# psu_and_discharge.net
KiCad netlist of a schematic drawn in Altium Designer
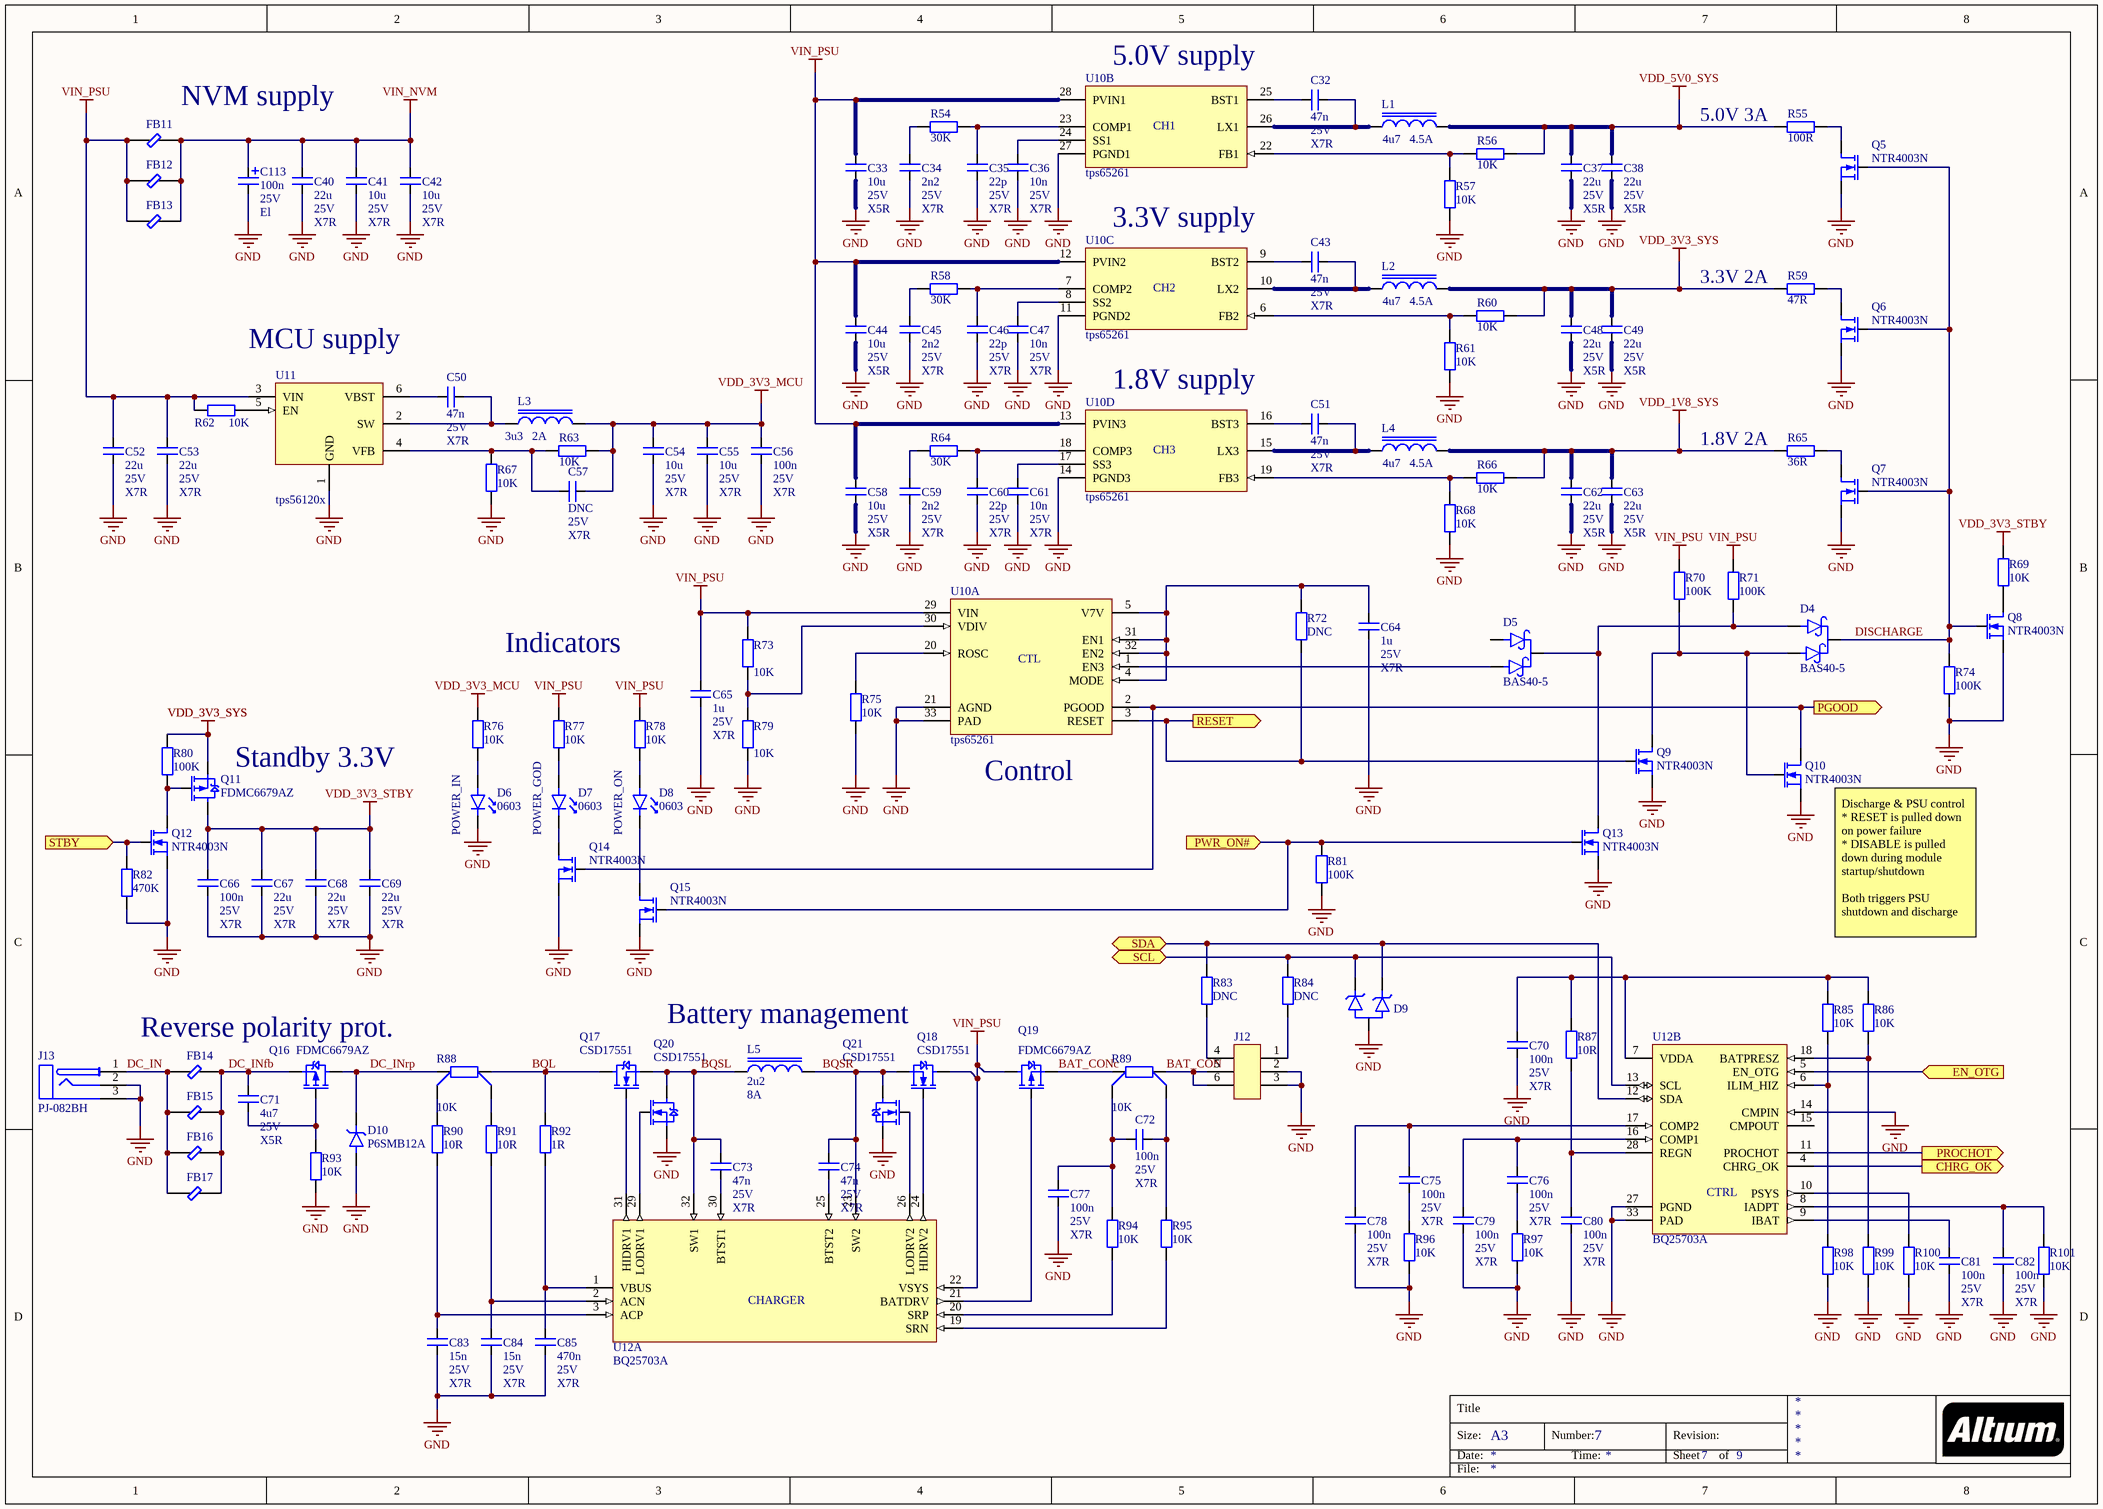
[diagram p0: psu_and_discharge.SchDoc]

(export (version "E")
  (design (tool "Eeschema 10.0.6"))
  (components
    (comp (ref "C32")
      (value "47n")
      (footprint "C1005[0402]")
      (description "Capacitor")
      (fields (field (name "VOLTAGE") "25V") (field (name "TYPE") "X7R") (field (name "Comment") "cap"))
      (libsource (lib "gpa_passives") (part "cap"))
    )
    (comp (ref "C33")
      (value "10u")
      (footprint "C3216[1206]")
      (description "Capacitor")
      (fields (field (name "VOLTAGE") "25V") (field (name "TYPE") "X5R") (field (name "Comment") "cap"))
      (libsource (lib "gpa_passives") (part "cap"))
    )
    (comp (ref "C34")
      (value "2n2")
      (footprint "C1005[0402]")
      (description "Capacitor")
      (fields (field (name "VOLTAGE") "25V") (field (name "TYPE") "X7R") (field (name "Comment") "cap"))
      (libsource (lib "gpa_passives") (part "cap"))
    )
    (comp (ref "C35")
      (value "22p")
      (footprint "C1005[0402]")
      (description "Capacitor")
      (fields (field (name "VOLTAGE") "25V") (field (name "TYPE") "X7R") (field (name "Comment") "cap"))
      (libsource (lib "gpa_passives") (part "cap"))
    )
    (comp (ref "C36")
      (value "10n")
      (footprint "C1005[0402]")
      (description "Capacitor")
      (fields (field (name "VOLTAGE") "25V") (field (name "TYPE") "X7R") (field (name "Comment") "cap"))
      (libsource (lib "gpa_passives") (part "cap"))
    )
    (comp (ref "C37")
      (value "22u")
      (footprint "C3216[1206]")
      (description "Capacitor")
      (fields (field (name "VOLTAGE") "25V") (field (name "TYPE") "X5R") (field (name "Comment") "cap"))
      (libsource (lib "gpa_passives") (part "cap"))
    )
    (comp (ref "C38")
      (value "22u")
      (footprint "C3216[1206]")
      (description "Capacitor")
      (fields (field (name "VOLTAGE") "25V") (field (name "TYPE") "X5R") (field (name "Comment") "cap"))
      (libsource (lib "gpa_passives") (part "cap"))
    )
    (comp (ref "C40")
      (value "22u")
      (footprint "C3216[1206]")
      (description "Capacitor")
      (fields (field (name "VOLTAGE") "25V") (field (name "TYPE") "X7R") (field (name "Comment") "cap"))
      (libsource (lib "gpa_passives") (part "cap"))
    )
    (comp (ref "C41")
      (value "10u")
      (footprint "C3216[1206]")
      (description "Capacitor")
      (fields (field (name "VOLTAGE") "25V") (field (name "TYPE") "X7R") (field (name "Comment") "cap"))
      (libsource (lib "gpa_passives") (part "cap"))
    )
    (comp (ref "C42")
      (value "10u")
      (footprint "C3216[1206]")
      (description "Capacitor")
      (fields (field (name "VOLTAGE") "25V") (field (name "TYPE") "X7R") (field (name "Comment") "cap"))
      (libsource (lib "gpa_passives") (part "cap"))
    )
    (comp (ref "C43")
      (value "47n")
      (footprint "C1005[0402]")
      (description "Capacitor")
      (fields (field (name "VOLTAGE") "25V") (field (name "TYPE") "X7R") (field (name "Comment") "cap"))
      (libsource (lib "gpa_passives") (part "cap"))
    )
    (comp (ref "C44")
      (value "10u")
      (footprint "C3216[1206]")
      (description "Capacitor")
      (fields (field (name "VOLTAGE") "25V") (field (name "TYPE") "X5R") (field (name "Comment") "cap"))
      (libsource (lib "gpa_passives") (part "cap"))
    )
    (comp (ref "C45")
      (value "2n2")
      (footprint "C1005[0402]")
      (description "Capacitor")
      (fields (field (name "VOLTAGE") "25V") (field (name "TYPE") "X7R") (field (name "Comment") "cap"))
      (libsource (lib "gpa_passives") (part "cap"))
    )
    (comp (ref "C46")
      (value "22p")
      (footprint "C1005[0402]")
      (description "Capacitor")
      (fields (field (name "VOLTAGE") "25V") (field (name "TYPE") "X7R") (field (name "Comment") "cap"))
      (libsource (lib "gpa_passives") (part "cap"))
    )
    (comp (ref "C47")
      (value "10n")
      (footprint "C1005[0402]")
      (description "Capacitor")
      (fields (field (name "VOLTAGE") "25V") (field (name "TYPE") "X7R") (field (name "Comment") "cap"))
      (libsource (lib "gpa_passives") (part "cap"))
    )
    (comp (ref "C48")
      (value "22u")
      (footprint "C3216[1206]")
      (description "Capacitor")
      (fields (field (name "VOLTAGE") "25V") (field (name "TYPE") "X5R") (field (name "Comment") "cap"))
      (libsource (lib "gpa_passives") (part "cap"))
    )
    (comp (ref "C49")
      (value "22u")
      (footprint "C3216[1206]")
      (description "Capacitor")
      (fields (field (name "VOLTAGE") "25V") (field (name "TYPE") "X5R") (field (name "Comment") "cap"))
      (libsource (lib "gpa_passives") (part "cap"))
    )
    (comp (ref "C50")
      (value "47n")
      (footprint "C1005[0402]")
      (description "Capacitor")
      (fields (field (name "VOLTAGE") "25V") (field (name "TYPE") "X7R") (field (name "Comment") "cap"))
      (libsource (lib "gpa_passives") (part "cap"))
    )
    (comp (ref "C51")
      (value "47n")
      (footprint "C1005[0402]")
      (description "Capacitor")
      (fields (field (name "VOLTAGE") "25V") (field (name "TYPE") "X7R") (field (name "Comment") "cap"))
      (libsource (lib "gpa_passives") (part "cap"))
    )
    (comp (ref "C52")
      (value "22u")
      (footprint "C3216[1206]")
      (description "Capacitor")
      (fields (field (name "VOLTAGE") "25V") (field (name "TYPE") "X7R") (field (name "Comment") "cap"))
      (libsource (lib "gpa_passives") (part "cap"))
    )
    (comp (ref "C53")
      (value "22u")
      (footprint "C3216[1206]")
      (description "Capacitor")
      (fields (field (name "VOLTAGE") "25V") (field (name "TYPE") "X7R") (field (name "Comment") "cap"))
      (libsource (lib "gpa_passives") (part "cap"))
    )
    (comp (ref "C54")
      (value "10u")
      (footprint "C3216[1206]")
      (description "Capacitor")
      (fields (field (name "VOLTAGE") "25V") (field (name "TYPE") "X7R") (field (name "Comment") "cap"))
      (libsource (lib "gpa_passives") (part "cap"))
    )
    (comp (ref "C55")
      (value "10u")
      (footprint "C3216[1206]")
      (description "Capacitor")
      (fields (field (name "VOLTAGE") "25V") (field (name "TYPE") "X7R") (field (name "Comment") "cap"))
      (libsource (lib "gpa_passives") (part "cap"))
    )
    (comp (ref "C56")
      (value "100n")
      (footprint "C1005[0402]")
      (description "Capacitor")
      (fields (field (name "VOLTAGE") "25V") (field (name "TYPE") "X7R") (field (name "Comment") "cap"))
      (libsource (lib "gpa_passives") (part "cap"))
    )
    (comp (ref "C57")
      (value "DNC")
      (footprint "C1005[0402]")
      (description "Capacitor")
      (fields (field (name "VOLTAGE") "25V") (field (name "TYPE") "X7R") (field (name "Comment") "cap"))
      (libsource (lib "gpa_passives") (part "cap"))
    )
    (comp (ref "C58")
      (value "10u")
      (footprint "C3216[1206]")
      (description "Capacitor")
      (fields (field (name "VOLTAGE") "25V") (field (name "TYPE") "X5R") (field (name "Comment") "cap"))
      (libsource (lib "gpa_passives") (part "cap"))
    )
    (comp (ref "C59")
      (value "2n2")
      (footprint "C1005[0402]")
      (description "Capacitor")
      (fields (field (name "VOLTAGE") "25V") (field (name "TYPE") "X7R") (field (name "Comment") "cap"))
      (libsource (lib "gpa_passives") (part "cap"))
    )
    (comp (ref "C60")
      (value "22p")
      (footprint "C1005[0402]")
      (description "Capacitor")
      (fields (field (name "VOLTAGE") "25V") (field (name "TYPE") "X7R") (field (name "Comment") "cap"))
      (libsource (lib "gpa_passives") (part "cap"))
    )
    (comp (ref "C61")
      (value "10n")
      (footprint "C1005[0402]")
      (description "Capacitor")
      (fields (field (name "VOLTAGE") "25V") (field (name "TYPE") "X7R") (field (name "Comment") "cap"))
      (libsource (lib "gpa_passives") (part "cap"))
    )
    (comp (ref "C62")
      (value "22u")
      (footprint "C3216[1206]")
      (description "Capacitor")
      (fields (field (name "VOLTAGE") "25V") (field (name "TYPE") "X5R") (field (name "Comment") "cap"))
      (libsource (lib "gpa_passives") (part "cap"))
    )
    (comp (ref "C63")
      (value "22u")
      (footprint "C3216[1206]")
      (description "Capacitor")
      (fields (field (name "VOLTAGE") "25V") (field (name "TYPE") "X5R") (field (name "Comment") "cap"))
      (libsource (lib "gpa_passives") (part "cap"))
    )
    (comp (ref "C64")
      (value "1u")
      (footprint "C2012[0805]")
      (description "Capacitor")
      (fields (field (name "VOLTAGE") "25V") (field (name "TYPE") "X7R") (field (name "Comment") "cap"))
      (libsource (lib "gpa_passives") (part "cap"))
    )
    (comp (ref "C65")
      (value "1u")
      (footprint "C2012[0805]")
      (description "Capacitor")
      (fields (field (name "VOLTAGE") "25V") (field (name "TYPE") "X7R") (field (name "Comment") "cap"))
      (libsource (lib "gpa_passives") (part "cap"))
    )
    (comp (ref "C66")
      (value "100n")
      (footprint "C1005[0402]")
      (description "Capacitor")
      (fields (field (name "VOLTAGE") "25V") (field (name "TYPE") "X7R") (field (name "Comment") "cap"))
      (libsource (lib "gpa_passives") (part "cap"))
    )
    (comp (ref "C67")
      (value "22u")
      (footprint "C1005[0402]")
      (description "Capacitor")
      (fields (field (name "VOLTAGE") "25V") (field (name "TYPE") "X7R") (field (name "Comment") "cap"))
      (libsource (lib "gpa_passives") (part "cap"))
    )
    (comp (ref "C68")
      (value "22u")
      (footprint "C1005[0402]")
      (description "Capacitor")
      (fields (field (name "VOLTAGE") "25V") (field (name "TYPE") "X7R") (field (name "Comment") "cap"))
      (libsource (lib "gpa_passives") (part "cap"))
    )
    (comp (ref "C69")
      (value "22u")
      (footprint "C1005[0402]")
      (description "Capacitor")
      (fields (field (name "VOLTAGE") "25V") (field (name "TYPE") "X7R") (field (name "Comment") "cap"))
      (libsource (lib "gpa_passives") (part "cap"))
    )
    (comp (ref "C70")
      (value "100n")
      (footprint "C1005[0402]")
      (description "Capacitor")
      (fields (field (name "VOLTAGE") "25V") (field (name "TYPE") "X7R") (field (name "Comment") "cap"))
      (libsource (lib "gpa_passives") (part "cap"))
    )
    (comp (ref "C71")
      (value "4u7")
      (footprint "C1005[0402]")
      (description "Capacitor")
      (fields (field (name "VOLTAGE") "25V") (field (name "TYPE") "X5R") (field (name "Comment") "cap"))
      (libsource (lib "gpa_passives") (part "cap"))
    )
    (comp (ref "C72")
      (value "100n")
      (footprint "C1005[0402]")
      (description "Capacitor")
      (fields (field (name "VOLTAGE") "25V") (field (name "TYPE") "X7R") (field (name "Comment") "cap"))
      (libsource (lib "gpa_passives") (part "cap"))
    )
    (comp (ref "C73")
      (value "47n")
      (footprint "C1005[0402]")
      (description "Capacitor")
      (fields (field (name "VOLTAGE") "25V") (field (name "TYPE") "X7R") (field (name "Comment") "cap"))
      (libsource (lib "gpa_passives") (part "cap"))
    )
    (comp (ref "C74")
      (value "47n")
      (footprint "C1005[0402]")
      (description "Capacitor")
      (fields (field (name "VOLTAGE") "25V") (field (name "TYPE") "X7R") (field (name "Comment") "cap"))
      (libsource (lib "gpa_passives") (part "cap"))
    )
    (comp (ref "C75")
      (value "100n")
      (footprint "C1005[0402]")
      (description "Capacitor")
      (fields (field (name "VOLTAGE") "25V") (field (name "TYPE") "X7R") (field (name "Comment") "cap"))
      (libsource (lib "gpa_passives") (part "cap"))
    )
    (comp (ref "C76")
      (value "100n")
      (footprint "C1005[0402]")
      (description "Capacitor")
      (fields (field (name "VOLTAGE") "25V") (field (name "TYPE") "X7R") (field (name "Comment") "cap"))
      (libsource (lib "gpa_passives") (part "cap"))
    )
    (comp (ref "C77")
      (value "100n")
      (footprint "C1005[0402]")
      (description "Capacitor")
      (fields (field (name "VOLTAGE") "25V") (field (name "TYPE") "X7R") (field (name "Comment") "cap"))
      (libsource (lib "gpa_passives") (part "cap"))
    )
    (comp (ref "C78")
      (value "100n")
      (footprint "C1005[0402]")
      (description "Capacitor")
      (fields (field (name "VOLTAGE") "25V") (field (name "TYPE") "X7R") (field (name "Comment") "cap"))
      (libsource (lib "gpa_passives") (part "cap"))
    )
    (comp (ref "C79")
      (value "100n")
      (footprint "C1005[0402]")
      (description "Capacitor")
      (fields (field (name "VOLTAGE") "25V") (field (name "TYPE") "X7R") (field (name "Comment") "cap"))
      (libsource (lib "gpa_passives") (part "cap"))
    )
    (comp (ref "C80")
      (value "100n")
      (footprint "C1005[0402]")
      (description "Capacitor")
      (fields (field (name "VOLTAGE") "25V") (field (name "TYPE") "X7R") (field (name "Comment") "cap"))
      (libsource (lib "gpa_passives") (part "cap"))
    )
    (comp (ref "C81")
      (value "100n")
      (footprint "C1005[0402]")
      (description "Capacitor")
      (fields (field (name "VOLTAGE") "25V") (field (name "TYPE") "X7R") (field (name "Comment") "cap"))
      (libsource (lib "gpa_passives") (part "cap"))
    )
    (comp (ref "C82")
      (value "100n")
      (footprint "C1005[0402]")
      (description "Capacitor")
      (fields (field (name "VOLTAGE") "25V") (field (name "TYPE") "X7R") (field (name "Comment") "cap"))
      (libsource (lib "gpa_passives") (part "cap"))
    )
    (comp (ref "C83")
      (value "15n")
      (footprint "C1005[0402]")
      (description "Capacitor")
      (fields (field (name "VOLTAGE") "25V") (field (name "TYPE") "X7R") (field (name "Comment") "cap"))
      (libsource (lib "gpa_passives") (part "cap"))
    )
    (comp (ref "C84")
      (value "15n")
      (footprint "C1005[0402]")
      (description "Capacitor")
      (fields (field (name "VOLTAGE") "25V") (field (name "TYPE") "X7R") (field (name "Comment") "cap"))
      (libsource (lib "gpa_passives") (part "cap"))
    )
    (comp (ref "C85")
      (value "470n")
      (footprint "C1005[0402]")
      (description "Capacitor")
      (fields (field (name "VOLTAGE") "25V") (field (name "TYPE") "X7R") (field (name "Comment") "cap"))
      (libsource (lib "gpa_passives") (part "cap"))
    )
    (comp (ref "C113")
      (value "100n")
      (footprint "CAPAE7366X55M")
      (description "Polarized capacitor")
      (fields (field (name "VOLTAGE") "25V") (field (name "TYPE") "El") (field (name "Comment") "pcap"))
      (libsource (lib "gpa_passives") (part "pcap"))
    )
    (comp (ref "D4")
      (value "BAS40-5")
      (footprint "DCC_SOT95P235X110-3N")
      (libsource (lib "gpa_actives") (part "diode_dual_cc"))
    )
    (comp (ref "D5")
      (value "BAS40-5")
      (footprint "DCC_SOT95P235X110-3N")
      (libsource (lib "gpa_actives") (part "diode_dual_cc"))
    )
    (comp (ref "D6")
      (value "0603")
      (footprint "LEDC1608X06N")
      (libsource (lib "gpa_actives") (part "diode_led"))
    )
    (comp (ref "D7")
      (value "0603")
      (footprint "LEDC1608X06N")
      (libsource (lib "gpa_actives") (part "diode_led"))
    )
    (comp (ref "D8")
      (value "0603")
      (footprint "LEDC1608X06N")
      (libsource (lib "gpa_actives") (part "diode_led"))
    )
    (comp (ref "D9")
      (value "Zener")
      (footprint "DCA_SOT95P235X110-3N")
      (fields (field (name "VOLTAGE") "3.6V"))
      (libsource (lib "gpa_actives") (part "diode_dual_ca_zener"))
    )
    (comp (ref "D10")
      (value "P6SMB12A")
      (footprint "SMA_DIOM5226X22N")
      (libsource (lib "gpa_actives") (part "diode_tvs_unidirectional"))
    )
    (comp (ref "FB11")
      (value "2506036007Y3")
      (footprint "FBC1608X07N")
      (description "Ferrite bead")
      (libsource (lib "gpa_passives") (part "ferrite_bead"))
    )
    (comp (ref "FB12")
      (value "2506036007Y3")
      (footprint "FBC1608X07N")
      (description "Ferrite bead")
      (libsource (lib "gpa_passives") (part "ferrite_bead"))
    )
    (comp (ref "FB13")
      (value "2506036007Y3")
      (footprint "FBC1608X07N")
      (description "Ferrite bead")
      (libsource (lib "gpa_passives") (part "ferrite_bead"))
    )
    (comp (ref "FB14")
      (value "2506036007Y3")
      (footprint "FBC1608X07N")
      (description "Ferrite bead")
      (libsource (lib "gpa_passives") (part "ferrite_bead"))
    )
    (comp (ref "FB15")
      (value "2506036007Y3")
      (footprint "FBC1608X07N")
      (description "Ferrite bead")
      (libsource (lib "gpa_passives") (part "ferrite_bead"))
    )
    (comp (ref "FB16")
      (value "2506036007Y3")
      (footprint "FBC1608X07N")
      (description "Ferrite bead")
      (libsource (lib "gpa_passives") (part "ferrite_bead"))
    )
    (comp (ref "FB17")
      (value "2506036007Y3")
      (footprint "FBC1608X07N")
      (description "Ferrite bead")
      (libsource (lib "gpa_passives") (part "ferrite_bead"))
    )
    (comp (ref "J12")
      (value "43045-0600")
      (footprint "molex_microfit_2x6_90deg")
      (libsource (lib "gpa_connectors") (part "microfit_2x3"))
    )
    (comp (ref "J13")
      (value "PJ-082BH")
      (footprint "CUI_DC_5.5MM_PJ028")
      (libsource (lib "gpa_connectors") (part "dc_jack_shielded"))
    )
    (comp (ref "L1")
      (value "4u7")
      (footprint "BOURNS_SRN6045TA-XXX")
      (fields (field (name "CURRENT") "4.5A") (field (name "Comment") "ASPI-0630LR-XXXM-T15"))
      (libsource (lib "gpa_passives") (part "ind"))
    )
    (comp (ref "L2")
      (value "4u7")
      (footprint "BOURNS_SRN6045TA-XXX")
      (fields (field (name "CURRENT") "4.5A") (field (name "Comment") "ASPI-0630LR-XXXM-T15"))
      (libsource (lib "gpa_passives") (part "ind"))
    )
    (comp (ref "L3")
      (value "3u3")
      (footprint "YUDEN_NRS4018T-XXXMDGJ")
      (fields (field (name "CURRENT") "2A") (field (name "Comment") "ASPI-0630LR-XXXM-T15"))
      (libsource (lib "gpa_passives") (part "ind"))
    )
    (comp (ref "L4")
      (value "4u7")
      (footprint "BOURNS_SRN6045TA-XXX")
      (fields (field (name "CURRENT") "4.5A") (field (name "Comment") "ASPI-0630LR-XXXM-T15"))
      (libsource (lib "gpa_passives") (part "ind"))
    )
    (comp (ref "L5")
      (value "2u2")
      (footprint "VISHAY_IHLM2525CZERXXXM01")
      (fields (field (name "CURRENT") "8A") (field (name "Comment") "ASPI-0630LR-XXXM-T15"))
      (libsource (lib "gpa_passives") (part "ind"))
    )
    (comp (ref "Q5")
      (value "NTR4003N")
      (footprint "NCH_SOT95P237X110-3N")
      (libsource (lib "gpa_actives") (part "nch_mosfet"))
    )
    (comp (ref "Q6")
      (value "NTR4003N")
      (footprint "NCH_SOT95P237X110-3N")
      (libsource (lib "gpa_actives") (part "nch_mosfet"))
    )
    (comp (ref "Q7")
      (value "NTR4003N")
      (footprint "NCH_SOT95P237X110-3N")
      (libsource (lib "gpa_actives") (part "nch_mosfet"))
    )
    (comp (ref "Q8")
      (value "NTR4003N")
      (footprint "NCH_SOT95P237X110-3N")
      (libsource (lib "gpa_actives") (part "nch_mosfet"))
    )
    (comp (ref "Q9")
      (value "NTR4003N")
      (footprint "NCH_SOT95P237X110-3N")
      (libsource (lib "gpa_actives") (part "nch_mosfet"))
    )
    (comp (ref "Q10")
      (value "NTR4003N")
      (footprint "NCH_SOT95P237X110-3N")
      (libsource (lib "gpa_actives") (part "nch_mosfet"))
    )
    (comp (ref "Q11")
      (value "FDMC6679AZ")
      (footprint "NCH_SON65P330X80_HS-9N")
      (libsource (lib "gpa_actives") (part "pch_mosfet_diode"))
    )
    (comp (ref "Q12")
      (value "NTR4003N")
      (footprint "NCH_SOT95P237X110-3N")
      (libsource (lib "gpa_actives") (part "nch_mosfet"))
    )
    (comp (ref "Q13")
      (value "NTR4003N")
      (footprint "NCH_SOT95P237X110-3N")
      (libsource (lib "gpa_actives") (part "nch_mosfet"))
    )
    (comp (ref "Q14")
      (value "NTR4003N")
      (footprint "NCH_SOT95P237X110-3N")
      (libsource (lib "gpa_actives") (part "nch_mosfet"))
    )
    (comp (ref "Q15")
      (value "NTR4003N")
      (footprint "NCH_SOT95P237X110-3N")
      (libsource (lib "gpa_actives") (part "nch_mosfet"))
    )
    (comp (ref "Q16")
      (value "FDMC6679AZ")
      (footprint "NCH_SON65P330X80_HS-9N")
      (libsource (lib "gpa_actives") (part "pch_mosfet_diode"))
    )
    (comp (ref "Q17")
      (value "CSD17551")
      (footprint "NCH_SON65P330X80_HS-9N")
      (libsource (lib "gpa_actives") (part "nch_mosfet_diode"))
    )
    (comp (ref "Q18")
      (value "CSD17551")
      (footprint "NCH_SON65P330X80_HS-9N")
      (libsource (lib "gpa_actives") (part "nch_mosfet_diode"))
    )
    (comp (ref "Q19")
      (value "FDMC6679AZ")
      (footprint "NCH_SON65P330X80_HS-9N")
      (libsource (lib "gpa_actives") (part "pch_mosfet_diode"))
    )
    (comp (ref "Q20")
      (value "CSD17551")
      (footprint "NCH_SON65P330X80_HS-9N")
      (libsource (lib "gpa_actives") (part "nch_mosfet_diode"))
    )
    (comp (ref "Q21")
      (value "CSD17551")
      (footprint "NCH_SON65P330X80_HS-9N")
      (libsource (lib "gpa_actives") (part "nch_mosfet_diode"))
    )
    (comp (ref "R54")
      (value "30K")
      (footprint "R1005[0402]")
      (description "Resistor")
      (fields (field (name "Comment") "res"))
      (libsource (lib "") (part "res_1"))
    )
    (comp (ref "R55")
      (value "100R")
      (footprint "R1005[0402]")
      (description "Resistor")
      (fields (field (name "Comment") "res"))
      (libsource (lib "") (part "res_1"))
    )
    (comp (ref "R56")
      (value "10K")
      (footprint "R1005[0402]")
      (description "Resistor")
      (fields (field (name "Comment") "res"))
      (libsource (lib "") (part "res_2"))
    )
    (comp (ref "R57")
      (value "10K")
      (footprint "R1005[0402]")
      (description "Resistor")
      (fields (field (name "Comment") "res"))
      (libsource (lib "") (part "res_3"))
    )
    (comp (ref "R58")
      (value "30K")
      (footprint "R1005[0402]")
      (description "Resistor")
      (fields (field (name "Comment") "res"))
      (libsource (lib "") (part "res_1"))
    )
    (comp (ref "R59")
      (value "47R")
      (footprint "R1005[0402]")
      (description "Resistor")
      (fields (field (name "Comment") "res"))
      (libsource (lib "") (part "res_1"))
    )
    (comp (ref "R60")
      (value "10K")
      (footprint "R1005[0402]")
      (description "Resistor")
      (fields (field (name "Comment") "res"))
      (libsource (lib "") (part "res_2"))
    )
    (comp (ref "R61")
      (value "10K")
      (footprint "R1005[0402]")
      (description "Resistor")
      (fields (field (name "Comment") "res"))
      (libsource (lib "") (part "res_3"))
    )
    (comp (ref "R62")
      (value "10K")
      (footprint "R1005[0402]")
      (description "Resistor")
      (fields (field (name "Comment") "res"))
      (libsource (lib "") (part "res_1"))
    )
    (comp (ref "R63")
      (value "10K")
      (footprint "R1005[0402]")
      (description "Resistor")
      (fields (field (name "Comment") "res"))
      (libsource (lib "") (part "res_1"))
    )
    (comp (ref "R64")
      (value "30K")
      (footprint "R1005[0402]")
      (description "Resistor")
      (fields (field (name "Comment") "res"))
      (libsource (lib "") (part "res_1"))
    )
    (comp (ref "R65")
      (value "36R")
      (footprint "R1005[0402]")
      (description "Resistor")
      (fields (field (name "Comment") "res"))
      (libsource (lib "") (part "res_1"))
    )
    (comp (ref "R66")
      (value "10K")
      (footprint "R1005[0402]")
      (description "Resistor")
      (fields (field (name "Comment") "res"))
      (libsource (lib "") (part "res_2"))
    )
    (comp (ref "R67")
      (value "10K")
      (footprint "R1005[0402]")
      (description "Resistor")
      (fields (field (name "Comment") "res"))
      (libsource (lib "gpa_passives") (part "res"))
    )
    (comp (ref "R68")
      (value "10K")
      (footprint "R1005[0402]")
      (description "Resistor")
      (fields (field (name "Comment") "res"))
      (libsource (lib "") (part "res_3"))
    )
    (comp (ref "R69")
      (value "10K")
      (footprint "R1005[0402]")
      (description "Resistor")
      (fields (field (name "Comment") "res"))
      (libsource (lib "gpa_passives") (part "res"))
    )
    (comp (ref "R70")
      (value "100K")
      (footprint "R1005[0402]")
      (description "Resistor")
      (fields (field (name "Comment") "res"))
      (libsource (lib "") (part "res_3"))
    )
    (comp (ref "R71")
      (value "100K")
      (footprint "R1005[0402]")
      (description "Resistor")
      (fields (field (name "Comment") "res"))
      (libsource (lib "") (part "res_3"))
    )
    (comp (ref "R72")
      (value "DNC")
      (footprint "R1005[0402]")
      (description "Resistor")
      (fields (field (name "Comment") "res"))
      (libsource (lib "") (part "res_3"))
    )
    (comp (ref "R73")
      (value "10K")
      (footprint "R1005[0402]")
      (description "Resistor")
      (fields (field (name "Comment") "res"))
      (libsource (lib "gpa_passives") (part "res"))
    )
    (comp (ref "R74")
      (value "100K")
      (footprint "R1005[0402]")
      (description "Resistor")
      (fields (field (name "Comment") "res"))
      (libsource (lib "gpa_passives") (part "res"))
    )
    (comp (ref "R75")
      (value "10K")
      (footprint "R1005[0402]")
      (description "Resistor")
      (fields (field (name "Comment") "res"))
      (libsource (lib "gpa_passives") (part "res"))
    )
    (comp (ref "R76")
      (value "10K")
      (footprint "R1005[0402]")
      (description "Resistor")
      (fields (field (name "Comment") "res"))
      (libsource (lib "gpa_passives") (part "res"))
    )
    (comp (ref "R77")
      (value "10K")
      (footprint "R1005[0402]")
      (description "Resistor")
      (fields (field (name "Comment") "res"))
      (libsource (lib "gpa_passives") (part "res"))
    )
    (comp (ref "R78")
      (value "10K")
      (footprint "R1005[0402]")
      (description "Resistor")
      (fields (field (name "Comment") "res"))
      (libsource (lib "gpa_passives") (part "res"))
    )
    (comp (ref "R79")
      (value "10K")
      (footprint "R1005[0402]")
      (description "Resistor")
      (fields (field (name "Comment") "res"))
      (libsource (lib "gpa_passives") (part "res"))
    )
    (comp (ref "R80")
      (value "100K")
      (footprint "R1005[0402]")
      (description "Resistor")
      (fields (field (name "Comment") "res"))
      (libsource (lib "gpa_passives") (part "res"))
    )
    (comp (ref "R81")
      (value "100K")
      (footprint "R1005[0402]")
      (description "Resistor")
      (fields (field (name "Comment") "res"))
      (libsource (lib "") (part "res_3"))
    )
    (comp (ref "R82")
      (value "470K")
      (footprint "R1005[0402]")
      (description "Resistor")
      (fields (field (name "Comment") "res"))
      (libsource (lib "gpa_passives") (part "res"))
    )
    (comp (ref "R83")
      (value "DNC")
      (footprint "R1005[0402]")
      (description "Resistor")
      (fields (field (name "Comment") "res"))
      (libsource (lib "") (part "res_3"))
    )
    (comp (ref "R84")
      (value "DNC")
      (footprint "R1005[0402]")
      (description "Resistor")
      (fields (field (name "Comment") "res"))
      (libsource (lib "") (part "res_3"))
    )
    (comp (ref "R85")
      (value "10K")
      (footprint "R1005[0402]")
      (description "Resistor")
      (fields (field (name "Comment") "res"))
      (libsource (lib "") (part "res_3"))
    )
    (comp (ref "R86")
      (value "10K")
      (footprint "R1005[0402]")
      (description "Resistor")
      (fields (field (name "Comment") "res"))
      (libsource (lib "") (part "res_3"))
    )
    (comp (ref "R87")
      (value "10R")
      (footprint "R1005[0402]")
      (description "Resistor")
      (fields (field (name "Comment") "res"))
      (libsource (lib "gpa_passives") (part "res"))
    )
    (comp (ref "R88")
      (value "10K")
      (footprint "4W_R320P320X90-4N")
      (description "Resistor")
      (fields (field (name "Comment") "res_sens"))
      (libsource (lib "gpa_passives") (part "res_sens"))
    )
    (comp (ref "R89")
      (value "10K")
      (footprint "4W_R320P320X90-4N")
      (description "Resistor")
      (fields (field (name "Comment") "res_sens"))
      (libsource (lib "") (part "res_sens_1"))
    )
    (comp (ref "R90")
      (value "10R")
      (footprint "R1005[0402]")
      (description "Resistor")
      (fields (field (name "Comment") "res"))
      (libsource (lib "gpa_passives") (part "res"))
    )
    (comp (ref "R91")
      (value "10R")
      (footprint "R1005[0402]")
      (description "Resistor")
      (fields (field (name "Comment") "res"))
      (libsource (lib "gpa_passives") (part "res"))
    )
    (comp (ref "R92")
      (value "1R")
      (footprint "R1005[0402]")
      (description "Resistor")
      (fields (field (name "Comment") "res"))
      (libsource (lib "gpa_passives") (part "res"))
    )
    (comp (ref "R93")
      (value "10K")
      (footprint "R1005[0402]")
      (description "Resistor")
      (fields (field (name "Comment") "res"))
      (libsource (lib "gpa_passives") (part "res"))
    )
    (comp (ref "R94")
      (value "10K")
      (footprint "R1005[0402]")
      (description "Resistor")
      (fields (field (name "Comment") "res"))
      (libsource (lib "gpa_passives") (part "res"))
    )
    (comp (ref "R95")
      (value "10K")
      (footprint "R1005[0402]")
      (description "Resistor")
      (fields (field (name "Comment") "res"))
      (libsource (lib "gpa_passives") (part "res"))
    )
    (comp (ref "R96")
      (value "10K")
      (footprint "R1005[0402]")
      (description "Resistor")
      (fields (field (name "Comment") "res"))
      (libsource (lib "gpa_passives") (part "res"))
    )
    (comp (ref "R97")
      (value "10K")
      (footprint "R1005[0402]")
      (description "Resistor")
      (fields (field (name "Comment") "res"))
      (libsource (lib "gpa_passives") (part "res"))
    )
    (comp (ref "R98")
      (value "10K")
      (footprint "R1005[0402]")
      (description "Resistor")
      (fields (field (name "Comment") "res"))
      (libsource (lib "") (part "res_3"))
    )
    (comp (ref "R99")
      (value "10K")
      (footprint "R1005[0402]")
      (description "Resistor")
      (fields (field (name "Comment") "res"))
      (libsource (lib "") (part "res_3"))
    )
    (comp (ref "R100")
      (value "10K")
      (footprint "R1005[0402]")
      (description "Resistor")
      (fields (field (name "Comment") "res"))
      (libsource (lib "gpa_passives") (part "res"))
    )
    (comp (ref "R101")
      (value "10K")
      (footprint "R1005[0402]")
      (description "Resistor")
      (fields (field (name "Comment") "res"))
      (libsource (lib "gpa_passives") (part "res"))
    )
    (comp (ref "U10")
      (value "tps65261")
      (footprint "TI_QFN50P500X500X100_HS-33M")
      (libsource (lib "gpa_ti") (part "tps65261"))
    )
    (comp (ref "U11")
      (value "tps56120x")
      (footprint "TI_SOT95P280X110-6N")
      (libsource (lib "gpa_ti") (part "tps56120x"))
    )
    (comp (ref "U12")
      (value "BQ25703A")
      (footprint "TI_QFN40P400X400X80_HS-33M")
      (libsource (lib "gpa_ti") (part "bq25703a"))
    )
  )
  (nets
    (net (code "1") (name "/BAT_CON") (class "Default")
      (node (ref "J12") (pin "5") (pintype "passive"))
      (node (ref "J12") (pin "6") (pintype "passive"))
      (node (ref "R89") (pin "2") (pinfunction "2_2") (pintype "passive"))
    )
    (net (code "2") (name "/BAT_CONc") (class "Default")
      (node (ref "Q19") (pin "S") (pinfunction "S_S") (pintype "passive"))
      (node (ref "R89") (pin "1") (pinfunction "1_1") (pintype "passive"))
    )
    (net (code "3") (name "/BQL") (class "Default")
      (node (ref "Q17") (pin "D") (pinfunction "D_D") (pintype "passive"))
      (node (ref "R88") (pin "1") (pinfunction "1_1") (pintype "passive"))
      (node (ref "R92") (pin "2") (pinfunction "2_2") (pintype "passive"))
    )
    (net (code "4") (name "/BQSL") (class "Default")
      (node (ref "C73") (pin "2") (pinfunction "2_2") (pintype "passive"))
      (node (ref "L5") (pin "1") (pinfunction "1_1") (pintype "passive"))
      (node (ref "Q17") (pin "S") (pinfunction "S_S") (pintype "passive"))
      (node (ref "Q20") (pin "D") (pinfunction "D_D") (pintype "passive"))
      (node (ref "U12") (pin "32") (pinfunction "SW1_32") (pintype "input"))
    )
    (net (code "5") (name "/BQSR") (class "Default")
      (node (ref "C74") (pin "2") (pinfunction "2_2") (pintype "passive"))
      (node (ref "L5") (pin "2") (pinfunction "2_2") (pintype "passive"))
      (node (ref "Q18") (pin "S") (pinfunction "S_S") (pintype "passive"))
      (node (ref "Q21") (pin "D") (pinfunction "D_D") (pintype "passive"))
      (node (ref "U12") (pin "23") (pinfunction "SW2_23") (pintype "input"))
    )
    (net (code "6") (name "/CHRG_OK") (class "Default")
      (node (ref "U12") (pin "4") (pinfunction "CHRG_OK_4") (pintype "open_collector"))
    )
    (net (code "7") (name "/DC_IN") (class "Default")
      (node (ref "FB14") (pin "1") (pinfunction "1_1") (pintype "passive"))
      (node (ref "FB15") (pin "1") (pinfunction "1_1") (pintype "passive"))
      (node (ref "FB16") (pin "1") (pinfunction "1_1") (pintype "passive"))
      (node (ref "FB17") (pin "1") (pinfunction "1_1") (pintype "passive"))
      (node (ref "J13") (pin "1") (pinfunction "1_1") (pintype "passive"))
    )
    (net (code "8") (name "/DC_INfb") (class "Default")
      (node (ref "C71") (pin "2") (pinfunction "2_2") (pintype "passive"))
      (node (ref "FB14") (pin "2") (pinfunction "2_2") (pintype "passive"))
      (node (ref "FB15") (pin "2") (pinfunction "2_2") (pintype "passive"))
      (node (ref "FB16") (pin "2") (pinfunction "2_2") (pintype "passive"))
      (node (ref "FB17") (pin "2") (pinfunction "2_2") (pintype "passive"))
      (node (ref "Q16") (pin "S") (pinfunction "S_S") (pintype "passive"))
    )
    (net (code "9") (name "/DC_INrp") (class "Default")
      (node (ref "D10") (pin "C") (pinfunction "C_C") (pintype "passive"))
      (node (ref "Q16") (pin "D") (pinfunction "D_D") (pintype "passive"))
      (node (ref "R88") (pin "2") (pinfunction "2_2") (pintype "passive"))
    )
    (net (code "10") (name "/DISCHARGE") (class "Default")
      (node (ref "D4") (pin "C") (pinfunction "C_C") (pintype "passive"))
      (node (ref "Q5") (pin "G") (pinfunction "G_G") (pintype "passive"))
      (node (ref "Q6") (pin "G") (pinfunction "G_G") (pintype "passive"))
      (node (ref "Q7") (pin "G") (pinfunction "G_G") (pintype "passive"))
      (node (ref "Q8") (pin "G") (pinfunction "G_G") (pintype "passive"))
      (node (ref "R74") (pin "2") (pinfunction "2_2") (pintype "passive"))
    )
    (net (code "11") (name "/EN_OTG") (class "Default")
      (node (ref "U12") (pin "5") (pinfunction "EN_OTG_5") (pintype "input"))
    )
    (net (code "12") (name "/PGOOD") (class "Default")
      (node (ref "Q10") (pin "D") (pinfunction "D_D") (pintype "passive"))
      (node (ref "Q14") (pin "G") (pinfunction "G_G") (pintype "passive"))
      (node (ref "U10") (pin "2") (pinfunction "PGOOD_2") (pintype "open_collector"))
    )
    (net (code "13") (name "/PROCHOT") (class "Default")
      (node (ref "U12") (pin "11") (pinfunction "PROCHOT_11") (pintype "open_collector"))
    )
    (net (code "14") (name "/PWR_ON#") (class "Default")
      (node (ref "Q13") (pin "G") (pinfunction "G_G") (pintype "passive"))
      (node (ref "Q15") (pin "G") (pinfunction "G_G") (pintype "passive"))
      (node (ref "R81") (pin "1") (pinfunction "1_1") (pintype "passive"))
    )
    (net (code "15") (name "/RESET") (class "Default")
      (node (ref "Q9") (pin "G") (pinfunction "G_G") (pintype "passive"))
      (node (ref "R72") (pin "2") (pinfunction "2_2") (pintype "passive"))
      (node (ref "U10") (pin "3") (pinfunction "RESET_3") (pintype "open_collector"))
    )
    (net (code "16") (name "/SCL") (class "Default")
      (node (ref "D9") (pin "C2") (pinfunction "C2_C2") (pintype "passive"))
      (node (ref "R84") (pin "1") (pinfunction "1_1") (pintype "passive"))
      (node (ref "U12") (pin "13") (pinfunction "SCL_13") (pintype "bidirectional"))
    )
    (net (code "17") (name "/SDA") (class "Default")
      (node (ref "D9") (pin "C1") (pinfunction "C1_C1") (pintype "passive"))
      (node (ref "R83") (pin "1") (pinfunction "1_1") (pintype "passive"))
      (node (ref "U12") (pin "12") (pinfunction "SDA_12") (pintype "bidirectional"))
    )
    (net (code "18") (name "/STBY") (class "Default")
      (node (ref "Q12") (pin "G") (pinfunction "G_G") (pintype "passive"))
      (node (ref "R82") (pin "2") (pinfunction "2_2") (pintype "passive"))
    )
    (net (code "19") (name "GND") (class "Default")
      (node (ref "C113") (pin "2") (pinfunction "2_2") (pintype "passive"))
      (node (ref "C33") (pin "1") (pinfunction "1_1") (pintype "passive"))
      (node (ref "C34") (pin "1") (pinfunction "1_1") (pintype "passive"))
      (node (ref "C35") (pin "1") (pinfunction "1_1") (pintype "passive"))
      (node (ref "C36") (pin "1") (pinfunction "1_1") (pintype "passive"))
      (node (ref "C37") (pin "1") (pinfunction "1_1") (pintype "passive"))
      (node (ref "C38") (pin "1") (pinfunction "1_1") (pintype "passive"))
      (node (ref "C40") (pin "1") (pinfunction "1_1") (pintype "passive"))
      (node (ref "C41") (pin "1") (pinfunction "1_1") (pintype "passive"))
      (node (ref "C42") (pin "1") (pinfunction "1_1") (pintype "passive"))
      (node (ref "C44") (pin "1") (pinfunction "1_1") (pintype "passive"))
      (node (ref "C45") (pin "1") (pinfunction "1_1") (pintype "passive"))
      (node (ref "C46") (pin "1") (pinfunction "1_1") (pintype "passive"))
      (node (ref "C47") (pin "1") (pinfunction "1_1") (pintype "passive"))
      (node (ref "C48") (pin "1") (pinfunction "1_1") (pintype "passive"))
      (node (ref "C49") (pin "1") (pinfunction "1_1") (pintype "passive"))
      (node (ref "C52") (pin "1") (pinfunction "1_1") (pintype "passive"))
      (node (ref "C53") (pin "1") (pinfunction "1_1") (pintype "passive"))
      (node (ref "C54") (pin "1") (pinfunction "1_1") (pintype "passive"))
      (node (ref "C55") (pin "1") (pinfunction "1_1") (pintype "passive"))
      (node (ref "C56") (pin "1") (pinfunction "1_1") (pintype "passive"))
      (node (ref "C58") (pin "1") (pinfunction "1_1") (pintype "passive"))
      (node (ref "C59") (pin "1") (pinfunction "1_1") (pintype "passive"))
      (node (ref "C60") (pin "1") (pinfunction "1_1") (pintype "passive"))
      (node (ref "C61") (pin "1") (pinfunction "1_1") (pintype "passive"))
      (node (ref "C62") (pin "1") (pinfunction "1_1") (pintype "passive"))
      (node (ref "C63") (pin "1") (pinfunction "1_1") (pintype "passive"))
      (node (ref "C64") (pin "1") (pinfunction "1_1") (pintype "passive"))
      (node (ref "C65") (pin "1") (pinfunction "1_1") (pintype "passive"))
      (node (ref "C66") (pin "1") (pinfunction "1_1") (pintype "passive"))
      (node (ref "C67") (pin "1") (pinfunction "1_1") (pintype "passive"))
      (node (ref "C68") (pin "1") (pinfunction "1_1") (pintype "passive"))
      (node (ref "C69") (pin "1") (pinfunction "1_1") (pintype "passive"))
      (node (ref "C70") (pin "1") (pinfunction "1_1") (pintype "passive"))
      (node (ref "C77") (pin "2") (pinfunction "2_2") (pintype "passive"))
      (node (ref "C78") (pin "2") (pinfunction "2_2") (pintype "passive"))
      (node (ref "C79") (pin "2") (pinfunction "2_2") (pintype "passive"))
      (node (ref "C80") (pin "2") (pinfunction "2_2") (pintype "passive"))
      (node (ref "C81") (pin "1") (pinfunction "1_1") (pintype "passive"))
      (node (ref "C82") (pin "1") (pinfunction "1_1") (pintype "passive"))
      (node (ref "C83") (pin "1") (pinfunction "1_1") (pintype "passive"))
      (node (ref "C84") (pin "1") (pinfunction "1_1") (pintype "passive"))
      (node (ref "C85") (pin "1") (pinfunction "1_1") (pintype "passive"))
      (node (ref "D10") (pin "A") (pinfunction "A_A") (pintype "passive"))
      (node (ref "D6") (pin "C") (pinfunction "C_C") (pintype "passive"))
      (node (ref "D9") (pin "A") (pinfunction "A_A") (pintype "passive"))
      (node (ref "J12") (pin "2") (pintype "passive"))
      (node (ref "J12") (pin "3") (pintype "passive"))
      (node (ref "J13") (pin "2") (pinfunction "2_2") (pintype "passive"))
      (node (ref "J13") (pin "3") (pinfunction "3_3") (pintype "passive"))
      (node (ref "Q10") (pin "S") (pinfunction "S_S") (pintype "passive"))
      (node (ref "Q12") (pin "S") (pinfunction "S_S") (pintype "passive"))
      (node (ref "Q13") (pin "S") (pinfunction "S_S") (pintype "passive"))
      (node (ref "Q14") (pin "S") (pinfunction "S_S") (pintype "passive"))
      (node (ref "Q15") (pin "S") (pinfunction "S_S") (pintype "passive"))
      (node (ref "Q20") (pin "S") (pinfunction "S_S") (pintype "passive"))
      (node (ref "Q21") (pin "S") (pinfunction "S_S") (pintype "passive"))
      (node (ref "Q5") (pin "S") (pinfunction "S_S") (pintype "passive"))
      (node (ref "Q6") (pin "S") (pinfunction "S_S") (pintype "passive"))
      (node (ref "Q7") (pin "S") (pinfunction "S_S") (pintype "passive"))
      (node (ref "Q8") (pin "S") (pinfunction "S_S") (pintype "passive"))
      (node (ref "Q9") (pin "S") (pinfunction "S_S") (pintype "passive"))
      (node (ref "R100") (pin "1") (pinfunction "1_1") (pintype "passive"))
      (node (ref "R101") (pin "1") (pinfunction "1_1") (pintype "passive"))
      (node (ref "R57") (pin "2") (pinfunction "2_2") (pintype "passive"))
      (node (ref "R61") (pin "2") (pinfunction "2_2") (pintype "passive"))
      (node (ref "R67") (pin "1") (pinfunction "1_1") (pintype "passive"))
      (node (ref "R68") (pin "2") (pinfunction "2_2") (pintype "passive"))
      (node (ref "R74") (pin "1") (pinfunction "1_1") (pintype "passive"))
      (node (ref "R75") (pin "1") (pinfunction "1_1") (pintype "passive"))
      (node (ref "R79") (pin "1") (pinfunction "1_1") (pintype "passive"))
      (node (ref "R81") (pin "2") (pinfunction "2_2") (pintype "passive"))
      (node (ref "R82") (pin "1") (pinfunction "1_1") (pintype "passive"))
      (node (ref "R93") (pin "1") (pinfunction "1_1") (pintype "passive"))
      (node (ref "R96") (pin "1") (pinfunction "1_1") (pintype "passive"))
      (node (ref "R97") (pin "1") (pinfunction "1_1") (pintype "passive"))
      (node (ref "R98") (pin "2") (pinfunction "2_2") (pintype "passive"))
      (node (ref "R99") (pin "2") (pinfunction "2_2") (pintype "passive"))
      (node (ref "U10") (pin "11") (pinfunction "PGND2_11") (pintype "power_in"))
      (node (ref "U10") (pin "14") (pinfunction "PGND3_14") (pintype "power_in"))
      (node (ref "U10") (pin "21") (pinfunction "AGND_21") (pintype "power_in"))
      (node (ref "U10") (pin "27") (pinfunction "PGND1_27") (pintype "power_in"))
      (node (ref "U10") (pin "33") (pinfunction "PAD_33") (pintype "power_in"))
      (node (ref "U11") (pin "1") (pinfunction "GND_1") (pintype "power_in"))
      (node (ref "U12") (pin "14") (pinfunction "CMPIN_14") (pintype "input"))
      (node (ref "U12") (pin "27") (pinfunction "PGND_27") (pintype "power_in"))
      (node (ref "U12") (pin "33") (pinfunction "PAD_33") (pintype "power_in"))
    )
    (net (code "20") (name "Net-(C34-Pad2)") (class "Default")
      (node (ref "C34") (pin "2") (pinfunction "2_2") (pintype "passive"))
      (node (ref "R54") (pin "1") (pinfunction "1_1") (pintype "passive"))
    )
    (net (code "21") (name "Net-(C45-Pad2)") (class "Default")
      (node (ref "C45") (pin "2") (pinfunction "2_2") (pintype "passive"))
      (node (ref "R58") (pin "1") (pinfunction "1_1") (pintype "passive"))
    )
    (net (code "22") (name "Net-(C59-Pad2)") (class "Default")
      (node (ref "C59") (pin "2") (pinfunction "2_2") (pintype "passive"))
      (node (ref "R64") (pin "1") (pinfunction "1_1") (pintype "passive"))
    )
    (net (code "23") (name "Net-(C71-Pad1)") (class "Default")
      (node (ref "C71") (pin "1") (pinfunction "1_1") (pintype "passive"))
      (node (ref "Q16") (pin "G") (pinfunction "G_G") (pintype "passive"))
      (node (ref "R93") (pin "2") (pinfunction "2_2") (pintype "passive"))
    )
    (net (code "24") (name "Net-(C72-Pad1)") (class "Default")
      (node (ref "C72") (pin "1") (pinfunction "1_1") (pintype "passive"))
      (node (ref "R89") (pin "S2") (pinfunction "S2_S2") (pintype "passive"))
      (node (ref "R95") (pin "2") (pinfunction "2_2") (pintype "passive"))
    )
    (net (code "25") (name "Net-(C72-Pad2)") (class "Default")
      (node (ref "C72") (pin "2") (pinfunction "2_2") (pintype "passive"))
      (node (ref "C77") (pin "1") (pinfunction "1_1") (pintype "passive"))
      (node (ref "R89") (pin "S1") (pinfunction "S1_S1") (pintype "passive"))
      (node (ref "R94") (pin "2") (pinfunction "2_2") (pintype "passive"))
    )
    (net (code "26") (name "Net-(C75-Pad2)") (class "Default")
      (node (ref "C75") (pin "2") (pinfunction "2_2") (pintype "passive"))
      (node (ref "R96") (pin "2") (pinfunction "2_2") (pintype "passive"))
    )
    (net (code "27") (name "Net-(C76-Pad2)") (class "Default")
      (node (ref "C76") (pin "2") (pinfunction "2_2") (pintype "passive"))
      (node (ref "R97") (pin "2") (pinfunction "2_2") (pintype "passive"))
    )
    (net (code "28") (name "Net-(D4-PadA1)") (class "Default")
      (node (ref "D4") (pin "A1") (pinfunction "A1_A1") (pintype "passive"))
      (node (ref "D5") (pin "C") (pinfunction "C_C") (pintype "passive"))
      (node (ref "Q13") (pin "D") (pinfunction "D_D") (pintype "passive"))
      (node (ref "R71") (pin "2") (pinfunction "2_2") (pintype "passive"))
    )
    (net (code "29") (name "Net-(D4-PadA2)") (class "Default")
      (node (ref "D4") (pin "A2") (pinfunction "A2_A2") (pintype "passive"))
      (node (ref "Q10") (pin "G") (pinfunction "G_G") (pintype "passive"))
      (node (ref "Q9") (pin "D") (pinfunction "D_D") (pintype "passive"))
      (node (ref "R70") (pin "2") (pinfunction "2_2") (pintype "passive"))
    )
    (net (code "30") (name "Net-(D6-PadA)") (class "Default")
      (node (ref "D6") (pin "A") (pinfunction "A_A") (pintype "passive"))
      (node (ref "R76") (pin "1") (pinfunction "1_1") (pintype "passive"))
    )
    (net (code "31") (name "Net-(D7-PadA)") (class "Default")
      (node (ref "D7") (pin "A") (pinfunction "A_A") (pintype "passive"))
      (node (ref "R77") (pin "1") (pinfunction "1_1") (pintype "passive"))
    )
    (net (code "32") (name "Net-(D7-PadC)") (class "Default")
      (node (ref "D7") (pin "C") (pinfunction "C_C") (pintype "passive"))
      (node (ref "Q14") (pin "D") (pinfunction "D_D") (pintype "passive"))
    )
    (net (code "33") (name "Net-(D8-PadA)") (class "Default")
      (node (ref "D8") (pin "A") (pinfunction "A_A") (pintype "passive"))
      (node (ref "R78") (pin "1") (pinfunction "1_1") (pintype "passive"))
    )
    (net (code "34") (name "Net-(D8-PadC)") (class "Default")
      (node (ref "D8") (pin "C") (pinfunction "C_C") (pintype "passive"))
      (node (ref "Q15") (pin "D") (pinfunction "D_D") (pintype "passive"))
    )
    (net (code "35") (name "Net-(J12-Pad1)") (class "Default")
      (node (ref "J12") (pin "1") (pintype "passive"))
      (node (ref "R84") (pin "2") (pinfunction "2_2") (pintype "passive"))
    )
    (net (code "36") (name "Net-(J12-Pad4)") (class "Default")
      (node (ref "J12") (pin "4") (pintype "passive"))
      (node (ref "R83") (pin "2") (pinfunction "2_2") (pintype "passive"))
    )
    (net (code "37") (name "Net-(Q5-PadD)") (class "Default")
      (node (ref "Q5") (pin "D") (pinfunction "D_D") (pintype "passive"))
      (node (ref "R55") (pin "2") (pinfunction "2_2") (pintype "passive"))
    )
    (net (code "38") (name "Net-(Q6-PadD)") (class "Default")
      (node (ref "Q6") (pin "D") (pinfunction "D_D") (pintype "passive"))
      (node (ref "R59") (pin "2") (pinfunction "2_2") (pintype "passive"))
    )
    (net (code "39") (name "Net-(Q7-PadD)") (class "Default")
      (node (ref "Q7") (pin "D") (pinfunction "D_D") (pintype "passive"))
      (node (ref "R65") (pin "2") (pinfunction "2_2") (pintype "passive"))
    )
    (net (code "40") (name "Net-(Q8-PadD)") (class "Default")
      (node (ref "Q8") (pin "D") (pinfunction "D_D") (pintype "passive"))
      (node (ref "R69") (pin "1") (pinfunction "1_1") (pintype "passive"))
    )
    (net (code "41") (name "Net-(Q11-PadG)") (class "Default")
      (node (ref "Q11") (pin "G") (pinfunction "G_G") (pintype "passive"))
      (node (ref "Q12") (pin "D") (pinfunction "D_D") (pintype "passive"))
      (node (ref "R80") (pin "1") (pinfunction "1_1") (pintype "passive"))
    )
    (net (code "42") (name "Net-(R88-PadS1)") (class "Default")
      (node (ref "R88") (pin "S1") (pinfunction "S1_S1") (pintype "passive"))
      (node (ref "R91") (pin "2") (pinfunction "2_2") (pintype "passive"))
    )
    (net (code "43") (name "Net-(R88-PadS2)") (class "Default")
      (node (ref "R88") (pin "S2") (pinfunction "S2_S2") (pintype "passive"))
      (node (ref "R90") (pin "2") (pinfunction "2_2") (pintype "passive"))
    )
    (net (code "44") (name "Net-(U10A-EN1)") (class "Default")
      (node (ref "C64") (pin "2") (pinfunction "2_2") (pintype "passive"))
      (node (ref "R72") (pin "1") (pinfunction "1_1") (pintype "passive"))
      (node (ref "U10") (pin "31") (pinfunction "EN1_31") (pintype "input"))
      (node (ref "U10") (pin "32") (pinfunction "EN2_32") (pintype "input"))
      (node (ref "U10") (pin "4") (pinfunction "MODE_4") (pintype "input"))
      (node (ref "U10") (pin "5") (pinfunction "V7V_5") (pintype "power_in"))
    )
    (net (code "45") (name "Net-(U10A-EN3)") (class "Default")
      (node (ref "D5") (pin "A2") (pinfunction "A2_A2") (pintype "passive"))
      (node (ref "U10") (pin "1") (pinfunction "EN3_1") (pintype "input"))
    )
    (net (code "46") (name "Net-(U10A-ROSC)") (class "Default")
      (node (ref "R75") (pin "2") (pinfunction "2_2") (pintype "passive"))
      (node (ref "U10") (pin "20") (pinfunction "ROSC_20") (pintype "input"))
    )
    (net (code "47") (name "Net-(U10A-VDIV)") (class "Default")
      (node (ref "R73") (pin "1") (pinfunction "1_1") (pintype "passive"))
      (node (ref "R79") (pin "2") (pinfunction "2_2") (pintype "passive"))
      (node (ref "U10") (pin "30") (pinfunction "VDIV_30") (pintype "input"))
    )
    (net (code "48") (name "Net-(U10B-BST1)") (class "Default")
      (node (ref "C32") (pin "2") (pinfunction "2_2") (pintype "passive"))
      (node (ref "U10") (pin "25") (pinfunction "BST1_25") (pintype "power_in"))
    )
    (net (code "49") (name "Net-(U10B-COMP1)") (class "Default")
      (node (ref "C35") (pin "2") (pinfunction "2_2") (pintype "passive"))
      (node (ref "R54") (pin "2") (pinfunction "2_2") (pintype "passive"))
      (node (ref "U10") (pin "23") (pinfunction "COMP1_23") (pintype "passive"))
    )
    (net (code "50") (name "Net-(U10B-FB1)") (class "Default")
      (node (ref "R56") (pin "2") (pinfunction "2_2") (pintype "passive"))
      (node (ref "R57") (pin "1") (pinfunction "1_1") (pintype "passive"))
      (node (ref "U10") (pin "22") (pinfunction "FB1_22") (pintype "input"))
    )
    (net (code "51") (name "Net-(U10B-LX1)") (class "Default")
      (node (ref "C32") (pin "1") (pinfunction "1_1") (pintype "passive"))
      (node (ref "L1") (pin "1") (pinfunction "1_1") (pintype "passive"))
      (node (ref "U10") (pin "26") (pinfunction "LX1_26") (pintype "power_in"))
    )
    (net (code "52") (name "Net-(U10B-SS1)") (class "Default")
      (node (ref "C36") (pin "2") (pinfunction "2_2") (pintype "passive"))
      (node (ref "U10") (pin "24") (pinfunction "SS1_24") (pintype "passive"))
    )
    (net (code "53") (name "Net-(U10C-BST2)") (class "Default")
      (node (ref "C43") (pin "2") (pinfunction "2_2") (pintype "passive"))
      (node (ref "U10") (pin "9") (pinfunction "BST2_9") (pintype "power_in"))
    )
    (net (code "54") (name "Net-(U10C-COMP2)") (class "Default")
      (node (ref "C46") (pin "2") (pinfunction "2_2") (pintype "passive"))
      (node (ref "R58") (pin "2") (pinfunction "2_2") (pintype "passive"))
      (node (ref "U10") (pin "7") (pinfunction "COMP2_7") (pintype "passive"))
    )
    (net (code "55") (name "Net-(U10C-FB2)") (class "Default")
      (node (ref "R60") (pin "2") (pinfunction "2_2") (pintype "passive"))
      (node (ref "R61") (pin "1") (pinfunction "1_1") (pintype "passive"))
      (node (ref "U10") (pin "6") (pinfunction "FB2_6") (pintype "input"))
    )
    (net (code "56") (name "Net-(U10C-LX2)") (class "Default")
      (node (ref "C43") (pin "1") (pinfunction "1_1") (pintype "passive"))
      (node (ref "L2") (pin "1") (pinfunction "1_1") (pintype "passive"))
      (node (ref "U10") (pin "10") (pinfunction "LX2_10") (pintype "power_in"))
    )
    (net (code "57") (name "Net-(U10C-SS2)") (class "Default")
      (node (ref "C47") (pin "2") (pinfunction "2_2") (pintype "passive"))
      (node (ref "U10") (pin "8") (pinfunction "SS2_8") (pintype "passive"))
    )
    (net (code "58") (name "Net-(U10D-BST3)") (class "Default")
      (node (ref "C51") (pin "2") (pinfunction "2_2") (pintype "passive"))
      (node (ref "U10") (pin "16") (pinfunction "BST3_16") (pintype "power_in"))
    )
    (net (code "59") (name "Net-(U10D-COMP3)") (class "Default")
      (node (ref "C60") (pin "2") (pinfunction "2_2") (pintype "passive"))
      (node (ref "R64") (pin "2") (pinfunction "2_2") (pintype "passive"))
      (node (ref "U10") (pin "18") (pinfunction "COMP3_18") (pintype "passive"))
    )
    (net (code "60") (name "Net-(U10D-FB3)") (class "Default")
      (node (ref "R66") (pin "2") (pinfunction "2_2") (pintype "passive"))
      (node (ref "R68") (pin "1") (pinfunction "1_1") (pintype "passive"))
      (node (ref "U10") (pin "19") (pinfunction "FB3_19") (pintype "input"))
    )
    (net (code "61") (name "Net-(U10D-LX3)") (class "Default")
      (node (ref "C51") (pin "1") (pinfunction "1_1") (pintype "passive"))
      (node (ref "L4") (pin "1") (pinfunction "1_1") (pintype "passive"))
      (node (ref "U10") (pin "15") (pinfunction "LX3_15") (pintype "power_in"))
    )
    (net (code "62") (name "Net-(U10D-SS3)") (class "Default")
      (node (ref "C61") (pin "2") (pinfunction "2_2") (pintype "passive"))
      (node (ref "U10") (pin "17") (pinfunction "SS3_17") (pintype "passive"))
    )
    (net (code "63") (name "Net-(U11-EN)") (class "Default")
      (node (ref "R62") (pin "2") (pinfunction "2_2") (pintype "passive"))
      (node (ref "U11") (pin "5") (pinfunction "EN_5") (pintype "input"))
    )
    (net (code "64") (name "Net-(U11-SW)") (class "Default")
      (node (ref "C50") (pin "1") (pinfunction "1_1") (pintype "passive"))
      (node (ref "L3") (pin "1") (pinfunction "1_1") (pintype "passive"))
      (node (ref "U11") (pin "2") (pinfunction "SW_2") (pintype "power_in"))
    )
    (net (code "65") (name "Net-(U11-VBST)") (class "Default")
      (node (ref "C50") (pin "2") (pinfunction "2_2") (pintype "passive"))
      (node (ref "U11") (pin "6") (pinfunction "VBST_6") (pintype "power_in"))
    )
    (net (code "66") (name "Net-(U11-VFB)") (class "Default")
      (node (ref "C57") (pin "2") (pinfunction "2_2") (pintype "passive"))
      (node (ref "R63") (pin "1") (pinfunction "1_1") (pintype "passive"))
      (node (ref "R67") (pin "2") (pinfunction "2_2") (pintype "passive"))
      (node (ref "U11") (pin "4") (pinfunction "VFB_4") (pintype "passive"))
    )
    (net (code "67") (name "Net-(U12A-ACN)") (class "Default")
      (node (ref "C84") (pin "2") (pinfunction "2_2") (pintype "passive"))
      (node (ref "R91") (pin "1") (pinfunction "1_1") (pintype "passive"))
      (node (ref "U12") (pin "2") (pinfunction "ACN_2") (pintype "input"))
    )
    (net (code "68") (name "Net-(U12A-ACP)") (class "Default")
      (node (ref "C83") (pin "2") (pinfunction "2_2") (pintype "passive"))
      (node (ref "R90") (pin "1") (pinfunction "1_1") (pintype "passive"))
      (node (ref "U12") (pin "3") (pinfunction "ACP_3") (pintype "input"))
    )
    (net (code "69") (name "Net-(U12A-BATDRV)") (class "Default")
      (node (ref "Q19") (pin "G") (pinfunction "G_G") (pintype "passive"))
      (node (ref "U12") (pin "21") (pinfunction "BATDRV_21") (pintype "output"))
    )
    (net (code "70") (name "Net-(U12A-BTST1)") (class "Default")
      (node (ref "C73") (pin "1") (pinfunction "1_1") (pintype "passive"))
      (node (ref "U12") (pin "30") (pinfunction "BTST1_30") (pintype "input"))
    )
    (net (code "71") (name "Net-(U12A-BTST2)") (class "Default")
      (node (ref "C74") (pin "1") (pinfunction "1_1") (pintype "passive"))
      (node (ref "U12") (pin "25") (pinfunction "BTST2_25") (pintype "input"))
    )
    (net (code "72") (name "Net-(U12A-HIDRV1)") (class "Default")
      (node (ref "Q17") (pin "G") (pinfunction "G_G") (pintype "passive"))
      (node (ref "U12") (pin "31") (pinfunction "HIDRV1_31") (pintype "output"))
    )
    (net (code "73") (name "Net-(U12A-HIDRV2)") (class "Default")
      (node (ref "Q18") (pin "G") (pinfunction "G_G") (pintype "passive"))
      (node (ref "U12") (pin "24") (pinfunction "HIDRV2_24") (pintype "output"))
    )
    (net (code "74") (name "Net-(U12A-LODRV1)") (class "Default")
      (node (ref "Q20") (pin "G") (pinfunction "G_G") (pintype "passive"))
      (node (ref "U12") (pin "29") (pinfunction "LODRV1_29") (pintype "output"))
    )
    (net (code "75") (name "Net-(U12A-LODRV2)") (class "Default")
      (node (ref "Q21") (pin "G") (pinfunction "G_G") (pintype "passive"))
      (node (ref "U12") (pin "26") (pinfunction "LODRV2_26") (pintype "output"))
    )
    (net (code "76") (name "Net-(U12A-SRN)") (class "Default")
      (node (ref "R95") (pin "1") (pinfunction "1_1") (pintype "passive"))
      (node (ref "U12") (pin "19") (pinfunction "SRN_19") (pintype "input"))
    )
    (net (code "77") (name "Net-(U12A-SRP)") (class "Default")
      (node (ref "R94") (pin "1") (pinfunction "1_1") (pintype "passive"))
      (node (ref "U12") (pin "20") (pinfunction "SRP_20") (pintype "input"))
    )
    (net (code "78") (name "Net-(U12A-VBUS)") (class "Default")
      (node (ref "C85") (pin "2") (pinfunction "2_2") (pintype "passive"))
      (node (ref "R92") (pin "1") (pinfunction "1_1") (pintype "passive"))
      (node (ref "U12") (pin "1") (pinfunction "VBUS_1") (pintype "power_in"))
    )
    (net (code "79") (name "Net-(U12B-BATPRESZ)") (class "Default")
      (node (ref "R86") (pin "2") (pinfunction "2_2") (pintype "passive"))
      (node (ref "R99") (pin "1") (pinfunction "1_1") (pintype "passive"))
      (node (ref "U12") (pin "18") (pinfunction "BATPRESZ_18") (pintype "input"))
    )
    (net (code "80") (name "Net-(U12B-COMP1)") (class "Default")
      (node (ref "C76") (pin "1") (pinfunction "1_1") (pintype "passive"))
      (node (ref "C79") (pin "1") (pinfunction "1_1") (pintype "passive"))
      (node (ref "U12") (pin "16") (pinfunction "COMP1_16") (pintype "input"))
    )
    (net (code "81") (name "Net-(U12B-COMP2)") (class "Default")
      (node (ref "C75") (pin "1") (pinfunction "1_1") (pintype "passive"))
      (node (ref "C78") (pin "1") (pinfunction "1_1") (pintype "passive"))
      (node (ref "U12") (pin "17") (pinfunction "COMP2_17") (pintype "input"))
    )
    (net (code "82") (name "Net-(U12B-IADPT)") (class "Default")
      (node (ref "C82") (pin "2") (pinfunction "2_2") (pintype "passive"))
      (node (ref "R101") (pin "2") (pinfunction "2_2") (pintype "passive"))
      (node (ref "U12") (pin "8") (pinfunction "IADPT_8") (pintype "output"))
    )
    (net (code "83") (name "Net-(U12B-IBAT)") (class "Default")
      (node (ref "C81") (pin "2") (pinfunction "2_2") (pintype "passive"))
      (node (ref "U12") (pin "9") (pinfunction "IBAT_9") (pintype "output"))
    )
    (net (code "84") (name "Net-(U12B-ILIM_HIZ)") (class "Default")
      (node (ref "R85") (pin "2") (pinfunction "2_2") (pintype "passive"))
      (node (ref "R98") (pin "1") (pinfunction "1_1") (pintype "passive"))
      (node (ref "U12") (pin "6") (pinfunction "ILIM_HIZ_6") (pintype "input"))
    )
    (net (code "85") (name "Net-(U12B-PSYS)") (class "Default")
      (node (ref "R100") (pin "2") (pinfunction "2_2") (pintype "passive"))
      (node (ref "U12") (pin "10") (pinfunction "PSYS_10") (pintype "output"))
    )
    (net (code "86") (name "Net-(U12B-REGN)") (class "Default")
      (node (ref "C80") (pin "1") (pinfunction "1_1") (pintype "passive"))
      (node (ref "R87") (pin "1") (pinfunction "1_1") (pintype "passive"))
      (node (ref "U12") (pin "28") (pinfunction "REGN_28") (pintype "power_in"))
    )
    (net (code "87") (name "Net-(U12B-VDDA)") (class "Default")
      (node (ref "C70") (pin "2") (pinfunction "2_2") (pintype "passive"))
      (node (ref "R85") (pin "1") (pinfunction "1_1") (pintype "passive"))
      (node (ref "R86") (pin "1") (pinfunction "1_1") (pintype "passive"))
      (node (ref "R87") (pin "2") (pinfunction "2_2") (pintype "passive"))
      (node (ref "U12") (pin "7") (pinfunction "VDDA_7") (pintype "power_in"))
    )
    (net (code "88") (name "VDD_1V8_SYS") (class "Default")
      (node (ref "C62") (pin "2") (pinfunction "2_2") (pintype "passive"))
      (node (ref "C63") (pin "2") (pinfunction "2_2") (pintype "passive"))
      (node (ref "L4") (pin "2") (pinfunction "2_2") (pintype "passive"))
      (node (ref "R65") (pin "1") (pinfunction "1_1") (pintype "passive"))
      (node (ref "R66") (pin "1") (pinfunction "1_1") (pintype "passive"))
    )
    (net (code "89") (name "VDD_3V3_MCU") (class "Default")
      (node (ref "C54") (pin "2") (pinfunction "2_2") (pintype "passive"))
      (node (ref "C55") (pin "2") (pinfunction "2_2") (pintype "passive"))
      (node (ref "C56") (pin "2") (pinfunction "2_2") (pintype "passive"))
      (node (ref "C57") (pin "1") (pinfunction "1_1") (pintype "passive"))
      (node (ref "L3") (pin "2") (pinfunction "2_2") (pintype "passive"))
      (node (ref "R63") (pin "2") (pinfunction "2_2") (pintype "passive"))
      (node (ref "R76") (pin "2") (pinfunction "2_2") (pintype "passive"))
    )
    (net (code "90") (name "VDD_3V3_STBY") (class "Default")
      (node (ref "C66") (pin "2") (pinfunction "2_2") (pintype "passive"))
      (node (ref "C67") (pin "2") (pinfunction "2_2") (pintype "passive"))
      (node (ref "C68") (pin "2") (pinfunction "2_2") (pintype "passive"))
      (node (ref "C69") (pin "2") (pinfunction "2_2") (pintype "passive"))
      (node (ref "Q11") (pin "D") (pinfunction "D_D") (pintype "passive"))
      (node (ref "R69") (pin "2") (pinfunction "2_2") (pintype "passive"))
    )
    (net (code "91") (name "VDD_3V3_SYS") (class "Default")
      (node (ref "C48") (pin "2") (pinfunction "2_2") (pintype "passive"))
      (node (ref "C49") (pin "2") (pinfunction "2_2") (pintype "passive"))
      (node (ref "L2") (pin "2") (pinfunction "2_2") (pintype "passive"))
      (node (ref "Q11") (pin "S") (pinfunction "S_S") (pintype "passive"))
      (node (ref "R59") (pin "1") (pinfunction "1_1") (pintype "passive"))
      (node (ref "R60") (pin "1") (pinfunction "1_1") (pintype "passive"))
      (node (ref "R80") (pin "2") (pinfunction "2_2") (pintype "passive"))
    )
    (net (code "92") (name "VDD_5V0_SYS") (class "Default")
      (node (ref "C37") (pin "2") (pinfunction "2_2") (pintype "passive"))
      (node (ref "C38") (pin "2") (pinfunction "2_2") (pintype "passive"))
      (node (ref "L1") (pin "2") (pinfunction "2_2") (pintype "passive"))
      (node (ref "R55") (pin "1") (pinfunction "1_1") (pintype "passive"))
      (node (ref "R56") (pin "1") (pinfunction "1_1") (pintype "passive"))
    )
    (net (code "93") (name "VIN_NVM") (class "Default")
      (node (ref "C113") (pin "1") (pinfunction "1_1") (pintype "passive"))
      (node (ref "C40") (pin "2") (pinfunction "2_2") (pintype "passive"))
      (node (ref "C41") (pin "2") (pinfunction "2_2") (pintype "passive"))
      (node (ref "C42") (pin "2") (pinfunction "2_2") (pintype "passive"))
      (node (ref "FB11") (pin "2") (pinfunction "2_2") (pintype "passive"))
      (node (ref "FB12") (pin "2") (pinfunction "2_2") (pintype "passive"))
      (node (ref "FB13") (pin "2") (pinfunction "2_2") (pintype "passive"))
    )
    (net (code "94") (name "VIN_PSU") (class "Default")
      (node (ref "C33") (pin "2") (pinfunction "2_2") (pintype "passive"))
      (node (ref "C44") (pin "2") (pinfunction "2_2") (pintype "passive"))
      (node (ref "C52") (pin "2") (pinfunction "2_2") (pintype "passive"))
      (node (ref "C53") (pin "2") (pinfunction "2_2") (pintype "passive"))
      (node (ref "C58") (pin "2") (pinfunction "2_2") (pintype "passive"))
      (node (ref "C65") (pin "2") (pinfunction "2_2") (pintype "passive"))
      (node (ref "FB11") (pin "1") (pinfunction "1_1") (pintype "passive"))
      (node (ref "FB12") (pin "1") (pinfunction "1_1") (pintype "passive"))
      (node (ref "FB13") (pin "1") (pinfunction "1_1") (pintype "passive"))
      (node (ref "Q18") (pin "D") (pinfunction "D_D") (pintype "passive"))
      (node (ref "Q19") (pin "D") (pinfunction "D_D") (pintype "passive"))
      (node (ref "R62") (pin "1") (pinfunction "1_1") (pintype "passive"))
      (node (ref "R70") (pin "1") (pinfunction "1_1") (pintype "passive"))
      (node (ref "R71") (pin "1") (pinfunction "1_1") (pintype "passive"))
      (node (ref "R73") (pin "2") (pinfunction "2_2") (pintype "passive"))
      (node (ref "R77") (pin "2") (pinfunction "2_2") (pintype "passive"))
      (node (ref "R78") (pin "2") (pinfunction "2_2") (pintype "passive"))
      (node (ref "U10") (pin "12") (pinfunction "PVIN2_12") (pintype "power_in"))
      (node (ref "U10") (pin "13") (pinfunction "PVIN3_13") (pintype "power_in"))
      (node (ref "U10") (pin "28") (pinfunction "PVIN1_28") (pintype "power_in"))
      (node (ref "U10") (pin "29") (pinfunction "VIN_29") (pintype "power_in"))
      (node (ref "U11") (pin "3") (pinfunction "VIN_3") (pintype "power_in"))
      (node (ref "U12") (pin "22") (pinfunction "VSYS_22") (pintype "input"))
    )
    (net (code "95") (name "unconnected-(D5-PadA1)") (class "Default")
      (node (ref "D5") (pin "A1") (pinfunction "A1_A1") (pintype "passive"))
    )
    (net (code "96") (name "unconnected-(U12B-CMPOUT-Pad15)") (class "Default")
      (node (ref "U12") (pin "15") (pinfunction "CMPOUT_15") (pintype "open_collector"))
    )
  )
)
